# CANDataDiodeSchematic-STM32F0-Rev7.net
KiCad netlist of a schematic drawn in Altium Designer
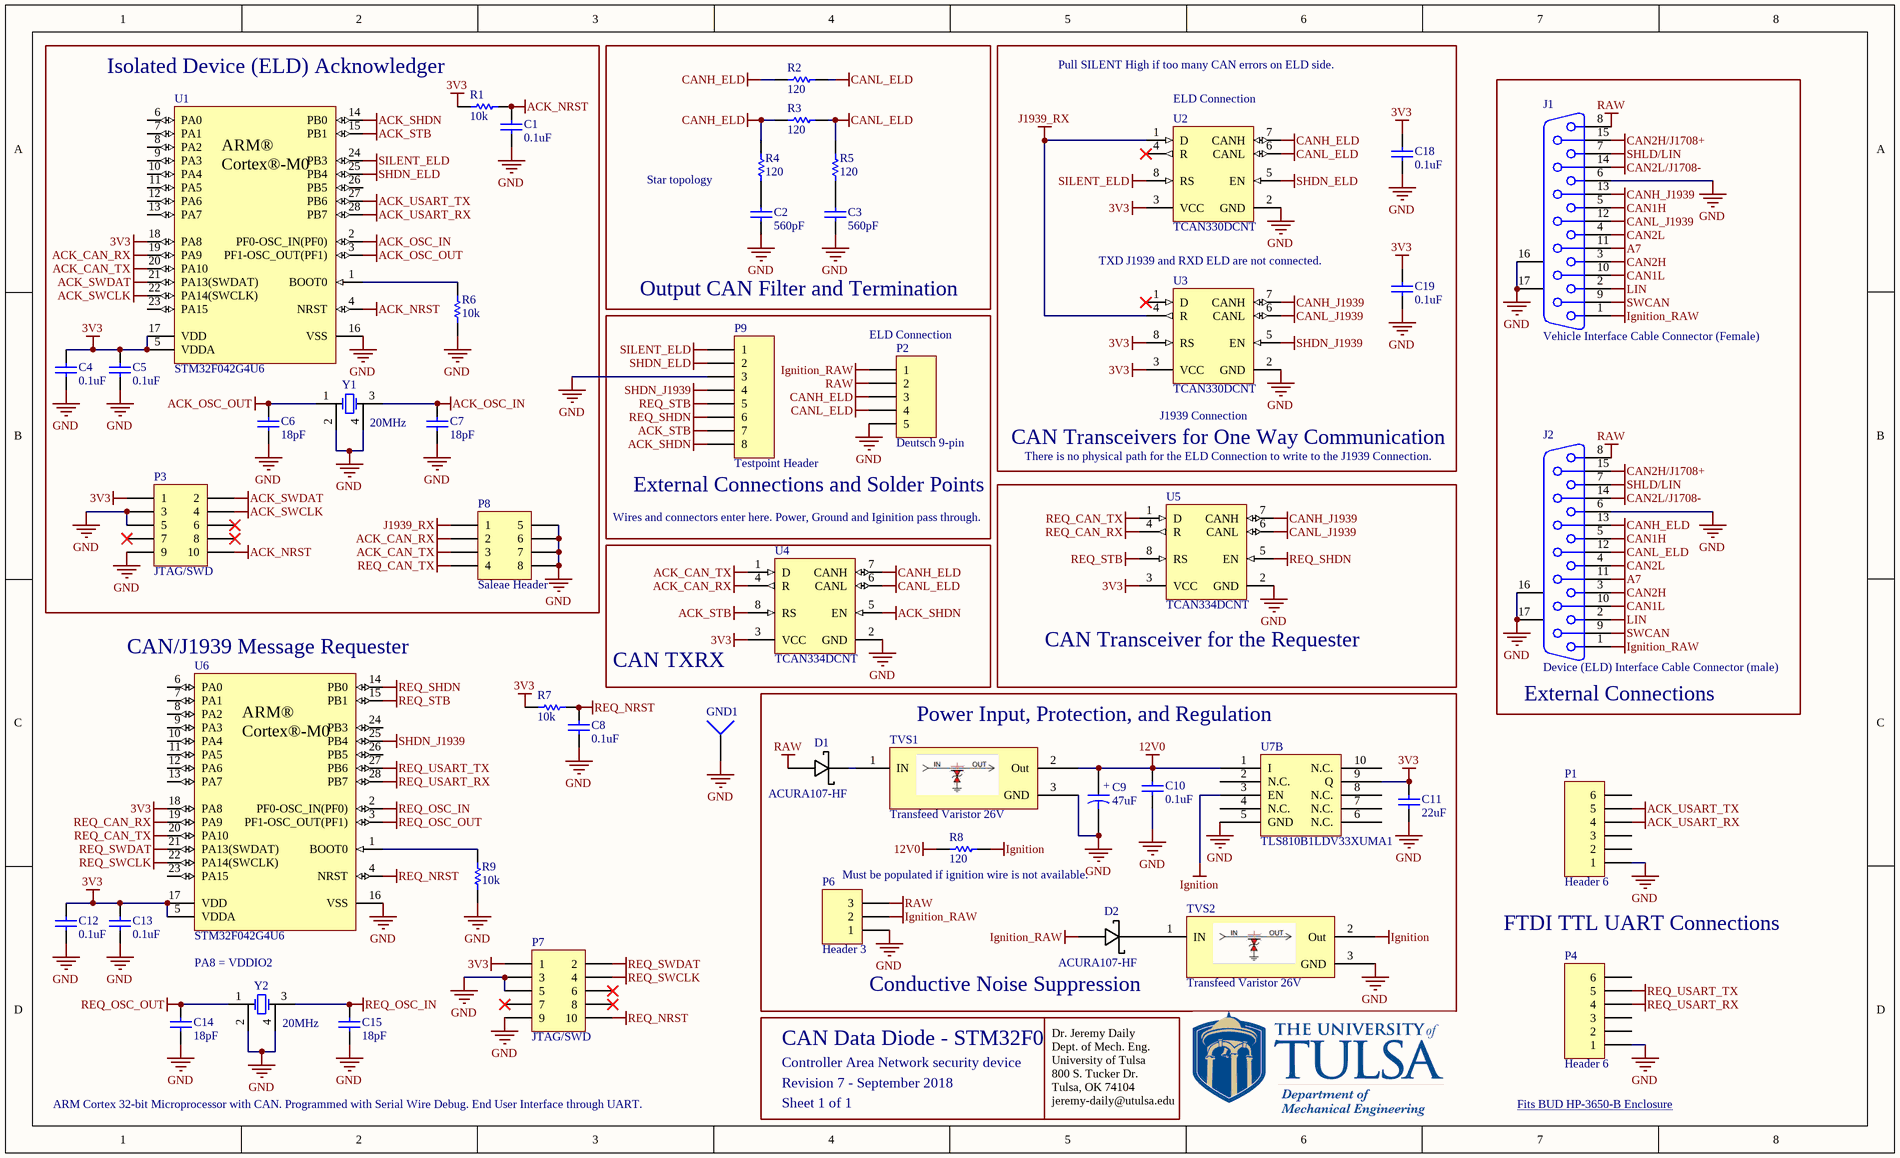
[diagram p0: CANDataDiodeSchematic-STM32F0-Rev7.SchDoc]

(export (version "E")
  (design (tool "Eeschema 10.0.6"))
  (components
    (comp (ref "C1")
      (value "0.1uF")
      (footprint "0402")
      (description "0.1µF ±10% 50V Ceramic Capacitor X7R 0402 (1005 Metric)")
      (fields
        (field (name "MANUFACTURER") "TDK Corporation")
        (field (name "PARTNUMBER") "CGA2B3X7R1H104K050BB")
      )
      (libsource (lib "SSS Integrated Library") (part "Cap"))
    )
    (comp (ref "C2")
      (value "560pF")
      (footprint "0402")
      (description "560pF ±5% 50V Ceramic Capacitor CH 0402 (1005 Metric)")
      (fields (field (name "MANUFACTURER") "Taiyo Yuden") (field (name "PARTNUMBER") "06031C561K4T2A"))
      (libsource (lib "SSS Integrated Library") (part "Cap"))
    )
    (comp (ref "C3")
      (value "560pF")
      (footprint "0402")
      (description "560pF ±5% 50V Ceramic Capacitor CH 0402 (1005 Metric)")
      (fields (field (name "MANUFACTURER") "Taiyo Yuden") (field (name "PARTNUMBER") "06031C561K4T2A"))
      (libsource (lib "SSS Integrated Library") (part "Cap"))
    )
    (comp (ref "C4")
      (value "0.1uF")
      (footprint "0402")
      (description "0.1µF ±10% 50V Ceramic Capacitor X7R 0402 (1005 Metric)")
      (fields
        (field (name "MANUFACTURER") "TDK Corporation")
        (field (name "PARTNUMBER") "CGA2B3X7R1H104K050BB")
      )
      (libsource (lib "SSS Integrated Library") (part "Cap"))
    )
    (comp (ref "C5")
      (value "0.1uF")
      (footprint "0402")
      (description "0.1µF ±10% 50V Ceramic Capacitor X7R 0402 (1005 Metric)")
      (fields
        (field (name "MANUFACTURER") "TDK Corporation")
        (field (name "PARTNUMBER") "CGA2B3X7R1H104K050BB")
      )
      (libsource (lib "SSS Integrated Library") (part "Cap"))
    )
    (comp (ref "C6")
      (value "18pF")
      (footprint "0402")
      (description "18pF ±5% 50V Ceramic Capacitor C0G, NP0 0402 (1005 Metric)")
      (fields
        (field (name "MANUFACTURER") "Murata Electronics North America")
        (field (name "PARTNUMBER") "GCM1555C1H180JA16D")
      )
      (libsource (lib "SSS Schematic Library") (part "Cap"))
    )
    (comp (ref "C7")
      (value "18pF")
      (footprint "0402")
      (description "18pF ±5% 50V Ceramic Capacitor C0G, NP0 0402 (1005 Metric)")
      (fields
        (field (name "MANUFACTURER") "Murata Electronics North America")
        (field (name "PARTNUMBER") "GCM1555C1H180JA16D")
      )
      (libsource (lib "SSS Schematic Library") (part "Cap"))
    )
    (comp (ref "C8")
      (value "0.1uF")
      (footprint "0402")
      (description "0.1µF ±10% 50V Ceramic Capacitor X7R 0402 (1005 Metric)")
      (fields
        (field (name "MANUFACTURER") "TDK Corporation")
        (field (name "PARTNUMBER") "CGA2B3X7R1H104K050BB")
      )
      (libsource (lib "SSS Integrated Library") (part "Cap"))
    )
    (comp (ref "C9")
      (value "47uF")
      (footprint "Elec. Cap - D")
      (description "47µF 35V Aluminum Capacitors Radial, Can - SMD 5000 Hrs @ 105°C")
      (fields
        (field (name "MANUFACTURER") "Panasonic Electronic Components")
        (field (name "PARTNUMBER") "EEE-HDV470XAP")
      )
      (libsource (lib "SSS Integrated Library") (part "Electrolytic Cap"))
    )
    (comp (ref "C10")
      (value "0.1uF")
      (footprint "0402")
      (description "0.1µF ±10% 50V Ceramic Capacitor X7R 0402 (1005 Metric)")
      (fields
        (field (name "MANUFACTURER") "TDK Corporation")
        (field (name "PARTNUMBER") "CGA2B3X7R1H104K050BB")
      )
      (libsource (lib "SSS Integrated Library") (part "Cap"))
    )
    (comp (ref "C11")
      (value "22uF")
      (footprint "1206")
      (description "22µF ±20% 4V Ceramic Capacitor X7R 1206 (3216 Metric)")
      (fields (field (name "MANUFACTURER") "Taiyo Yuden") (field (name "PARTNUMBER") "AMK316AB7226MLHT"))
      (libsource (lib "SSS Integrated Library") (part "Cap"))
    )
    (comp (ref "C12")
      (value "0.1uF")
      (footprint "0402")
      (description "0.1µF ±10% 50V Ceramic Capacitor X7R 0402 (1005 Metric)")
      (fields
        (field (name "MANUFACTURER") "TDK Corporation")
        (field (name "PARTNUMBER") "CGA2B3X7R1H104K050BB")
      )
      (libsource (lib "SSS Integrated Library") (part "Cap"))
    )
    (comp (ref "C13")
      (value "0.1uF")
      (footprint "0402")
      (description "0.1µF ±10% 50V Ceramic Capacitor X7R 0402 (1005 Metric)")
      (fields
        (field (name "MANUFACTURER") "TDK Corporation")
        (field (name "PARTNUMBER") "CGA2B3X7R1H104K050BB")
      )
      (libsource (lib "SSS Integrated Library") (part "Cap"))
    )
    (comp (ref "C14")
      (value "18pF")
      (footprint "0402")
      (description "18pF ±5% 50V Ceramic Capacitor C0G, NP0 0402 (1005 Metric)")
      (fields
        (field (name "MANUFACTURER") "Murata Electronics North America")
        (field (name "PARTNUMBER") "GCM1555C1H180JA16D")
      )
      (libsource (lib "SSS Schematic Library") (part "Cap"))
    )
    (comp (ref "C15")
      (value "18pF")
      (footprint "0402")
      (description "18pF ±5% 50V Ceramic Capacitor C0G, NP0 0402 (1005 Metric)")
      (fields
        (field (name "MANUFACTURER") "Murata Electronics North America")
        (field (name "PARTNUMBER") "GCM1555C1H180JA16D")
      )
      (libsource (lib "SSS Schematic Library") (part "Cap"))
    )
    (comp (ref "C18")
      (value "0.1uF")
      (footprint "0402")
      (description "0.1µF ±10% 50V Ceramic Capacitor X7R 0402 (1005 Metric)")
      (fields
        (field (name "MANUFACTURER") "TDK Corporation")
        (field (name "PARTNUMBER") "CGA2B3X7R1H104K050BB")
      )
      (libsource (lib "SSS Integrated Library") (part "Cap"))
    )
    (comp (ref "C19")
      (value "0.1uF")
      (footprint "0402")
      (description "0.1µF ±10% 50V Ceramic Capacitor X7R 0402 (1005 Metric)")
      (fields
        (field (name "MANUFACTURER") "TDK Corporation")
        (field (name "PARTNUMBER") "CGA2B3X7R1H104K050BB")
      )
      (libsource (lib "SSS Integrated Library") (part "Cap"))
    )
    (comp (ref "D1")
      (value "ACURA107-HF")
      (footprint "SMA with A and K")
      (description "Diode Schottky 1000V 1A Surface Mount DO-214AC (SMA)")
      (fields (field (name "MANUFACTURER") "Comchip Technology"))
      (libsource (lib "SSS Integrated Library") (part "Schottky Diode"))
    )
    (comp (ref "D2")
      (value "ACURA107-HF")
      (footprint "SMA with A and K")
      (description "Diode Schottky 1000V 1A Surface Mount DO-214AC (SMA)")
      (fields (field (name "MANUFACTURER") "Comchip Technology"))
      (libsource (lib "SSS Integrated Library") (part "Schottky Diode"))
    )
    (comp (ref "GND1")
      (value "Socket")
      (footprint "PIN1")
      (libsource (lib "Miscellaneous Connectors") (part "Socket"))
    )
    (comp (ref "J1")
      (value "Vehicle Interface Cable Connector (Female)")
      (footprint "DSUB1.385-2H15")
      (description "Receptacle Assembly, 15 Position, Right Angle")
      (fields (field (name "MANUFACTURER") "Amphenol FCI") (field (name "PARTNUMBER") "D15S33E4GV00LF"))
      (libsource (lib "Miscellaneous Connectors") (part "D Connector 15"))
    )
    (comp (ref "J2")
      (value "Device (ELD) Interface Cable Connector (male)")
      (footprint "DSUB1.385-2H15")
      (description "Receptacle Assembly, 15 Position, Right Angle")
      (fields (field (name "MANUFACTURER") "Amphenol FCI") (field (name "PARTNUMBER") "D15P33E4GV00LF"))
      (libsource (lib "Miscellaneous Connectors") (part "D Connector 15"))
    )
    (comp (ref "P1")
      (value "Header 6")
      (footprint "HDR1X6")
      (description "Header, 6-Pin")
      (fields
        (field (name "MANUFACTURER") "Sullins Connector Solutions")
        (field (name "PARTNUMBER") "PBC06SFAN")
      )
      (libsource (lib "Miscellaneous Connectors") (part "Header 6"))
    )
    (comp (ref "P2")
      (value "Deutsch 9-pin")
      (footprint "HDR1X5")
      (description "Pins A,B C, D oin the J1939 connector")
      (libsource (lib "Miscellaneous Connectors") (part "Header 5"))
    )
    (comp (ref "P3")
      (value "JTAG/SWD")
      (footprint "MHDR2X5")
      (description "Connector Header Through Hole 10 position 0.050\" (1.27mm)")
      (fields (field (name "MANUFACTURER") "CNC Tech") (field (name "PARTNUMBER") "1175-1627-ND"))
      (libsource (lib "Miscellaneous Connectors") (part "MHDR2X5"))
    )
    (comp (ref "P4")
      (value "Header 6")
      (footprint "HDR1X6")
      (description "Header, 6-Pin")
      (fields
        (field (name "MANUFACTURER") "Sullins Connector Solutions")
        (field (name "PARTNUMBER") "PBC06SFAN")
      )
      (libsource (lib "Miscellaneous Connectors") (part "Header 6"))
    )
    (comp (ref "P6")
      (value "Header 3")
      (footprint "HDR1X3")
      (description "Header, 3-Pin")
      (libsource (lib "Miscellaneous Connectors") (part "Header 3"))
    )
    (comp (ref "P7")
      (value "JTAG/SWD")
      (footprint "MHDR2X5")
      (description "Header, 5-Pin, Dual row")
      (fields (field (name "MANUFACTURER") "CNC Tech") (field (name "PARTNUMBER") "1175-1627-ND"))
      (libsource (lib "Miscellaneous Connectors") (part "MHDR2X5"))
    )
    (comp (ref "P8")
      (value "Saleae Header")
      (footprint "HDR2X4_CEN")
      (description "Header, 4-Pin, Dual row")
      (libsource (lib "Miscellaneous Connectors") (part "Header 4X2A"))
    )
    (comp (ref "P9")
      (value "Testpoint Header")
      (footprint "HDR1X8")
      (description "Header, 8-Pin")
      (libsource (lib "Miscellaneous Connectors") (part "Header 8"))
    )
    (comp (ref "R1")
      (value "10k")
      (footprint "0402")
      (fields (field (name "MANUFACTURER") "Susumu") (field (name "PARTNUMBER") "RG1005P-103-D-T10"))
      (libsource (lib "SSS Integrated Library") (part "Chip Resistor"))
    )
    (comp (ref "R2")
      (value "120")
      (footprint "0402")
      (description "120 Ohms ±1% 0.063W, 1/16W Chip Resistor 0402 (1005 Metric) Automotive AEC-Q200 Thick Film")
      (fields (field (name "MANUFACTURER") "Vishay Dale") (field (name "PARTNUMBER") "CRCW0402120RFKED"))
      (libsource (lib "SSS Integrated Library") (part "Chip Resistor"))
    )
    (comp (ref "R3")
      (value "120")
      (footprint "0402")
      (description "120 Ohms ±1% 0.063W, 1/16W Chip Resistor 0402 (1005 Metric) Automotive AEC-Q200 Thick Film")
      (fields (field (name "MANUFACTURER") "Vishay Dale") (field (name "PARTNUMBER") "CRCW0402120RFKED"))
      (libsource (lib "SSS Integrated Library") (part "Chip Resistor"))
    )
    (comp (ref "R4")
      (value "120")
      (footprint "0402")
      (description "120 Ohms ±1% 0.063W, 1/16W Chip Resistor 0402 (1005 Metric) Automotive AEC-Q200 Thick Film")
      (fields (field (name "MANUFACTURER") "Vishay Dale") (field (name "PARTNUMBER") "CRCW0402120RFKED"))
      (libsource (lib "SSS Integrated Library") (part "Chip Resistor"))
    )
    (comp (ref "R5")
      (value "120")
      (footprint "0402")
      (description "120 Ohms ±1% 0.063W, 1/16W Chip Resistor 0402 (1005 Metric) Automotive AEC-Q200 Thick Film")
      (fields (field (name "MANUFACTURER") "Vishay Dale") (field (name "PARTNUMBER") "CRCW0402120RFKED"))
      (libsource (lib "SSS Integrated Library") (part "Chip Resistor"))
    )
    (comp (ref "R6")
      (value "10k")
      (footprint "0402")
      (fields (field (name "MANUFACTURER") "Susumu") (field (name "PARTNUMBER") "RG1005P-103-D-T10"))
      (libsource (lib "SSS Integrated Library") (part "Chip Resistor"))
    )
    (comp (ref "R7")
      (value "10k")
      (footprint "0402")
      (fields (field (name "MANUFACTURER") "Susumu") (field (name "PARTNUMBER") "RG1005P-103-D-T10"))
      (libsource (lib "SSS Integrated Library") (part "Chip Resistor"))
    )
    (comp (ref "R8")
      (value "120")
      (footprint "0402")
      (description "120 Ohms ±1% 0.063W, 1/16W Chip Resistor 0402 (1005 Metric) Automotive AEC-Q200 Thick Film")
      (fields (field (name "MANUFACTURER") "Vishay Dale") (field (name "PARTNUMBER") "CRCW0402120RFKED"))
      (libsource (lib "SSS Integrated Library") (part "Chip Resistor"))
    )
    (comp (ref "R9")
      (value "10k")
      (footprint "0402")
      (fields (field (name "MANUFACTURER") "Susumu") (field (name "PARTNUMBER") "RG1005P-103-D-T10"))
      (libsource (lib "SSS Integrated Library") (part "Chip Resistor"))
    )
    (comp (ref "TVS1")
      (value "Transfeed Varistor 26V")
      (footprint "Transfeed")
      (description "34.5V 80A Varistor 1 Circuit Surface Mount 0805 (2012 Metric)")
      (fields (field (name "MANUFACTURER") "AVX") (field (name "PARTNUMBER") "V2AF126C600Y2EDP"))
      (libsource (lib "TU Custom Parts Schematics") (part "Transfeed"))
    )
    (comp (ref "TVS2")
      (value "Transfeed Varistor 26V")
      (footprint "Transfeed")
      (description "34.5V 80A Varistor 1 Circuit Surface Mount 0805 (2012 Metric)")
      (fields (field (name "MANUFACTURER") "AVX") (field (name "PARTNUMBER") "V2AF126C600Y2EDP"))
      (libsource (lib "TU Custom Parts Schematics") (part "Transfeed"))
    )
    (comp (ref "U1")
      (value "STM32F042G4U6")
      (footprint "STM-UFQFPN28_V")
      (description "ARM® Cortex®-M0 STM32F0 Microcontroller IC 32-Bit 48MHz 16KB (16K x 8) FLASH 28-UFQFPN (4x4)")
      (fields (field (name "MANUFACTURER") "STMicroelectronics"))
      (libsource (lib "STMicroelectronics STM32 F0") (part "STM32F050G4U6"))
    )
    (comp (ref "U2")
      (value "TCAN330DCNT")
      (footprint "SOT65P280X145-8N")
      (description "IC TXRX CAN 3.3V SOT23-8")
      (fields (field (name "MANUFACTURER") "Texas Instruments"))
      (libsource (lib "Texas Instruments Interface CAN") (part "SN65HVD234DR"))
    )
    (comp (ref "U3")
      (value "TCAN330DCNT")
      (footprint "SOT65P280X145-8N")
      (description "IC TXRX CAN 3.3V SOT23-8")
      (fields (field (name "MANUFACTURER") "Texas Instruments"))
      (libsource (lib "Texas Instruments Interface CAN") (part "SN65HVD234DR"))
    )
    (comp (ref "U4")
      (value "TCAN334DCNT")
      (footprint "SOT65P280X145-8N")
      (description "IC TXRX CAN 3.3V SOT23-8")
      (fields (field (name "MANUFACTURER") "Texas Instruments"))
      (libsource (lib "Texas Instruments Interface CAN") (part "SN65HVD234DR"))
    )
    (comp (ref "U5")
      (value "TCAN334DCNT")
      (footprint "SOT65P280X145-8N")
      (description "IC TXRX CAN 3.3V SOT23-8")
      (fields (field (name "MANUFACTURER") "Texas Instruments"))
      (libsource (lib "Texas Instruments Interface CAN") (part "SN65HVD234DR"))
    )
    (comp (ref "U6")
      (value "STM32F042G4U6")
      (footprint "STM-UFQFPN28_V")
      (description "ARM® Cortex®-M0 STM32F0 Microcontroller IC 32-Bit 48MHz 16KB (16K x 8) FLASH 28-UFQFPN (4x4)")
      (fields (field (name "MANUFACTURER") "STMicroelectronics"))
      (libsource (lib "STMicroelectronics STM32 F0") (part "STM32F050G4U6"))
    )
    (comp (ref "U7")
      (value "TLS810B1LDV33XUMA1")
      (footprint "SON50P330X110_HS-11N")
      (description "Linear Voltage Regulator IC  1 Output  100mA PG-TSON-10")
      (fields (field (name "MANUFACTURER") "Infineon Technologies"))
      (libsource (lib "CANDataDiode Schematic Library") (part "TLS810B1"))
    )
    (comp (ref "Y1")
      (value "20MHz")
      (footprint "XTAL 4 pad")
      (description "20MHz ±30ppm Crystal 18pF 60 Ohms 4-SMD, No Lead")
      (fields (field (name "MANUFACTURER") "ECS Inc.") (field (name "PARTNUMBER") "ECS-200-18-33Q-DS"))
      (libsource (lib "TU Custom Parts Schematics") (part "Crystal with Ground"))
    )
    (comp (ref "Y2")
      (value "20MHz")
      (footprint "XTAL 4 pad")
      (description "20MHz ±30ppm Crystal 18pF 60 Ohms 4-SMD, No Lead")
      (fields (field (name "MANUFACTURER") "ECS Inc.") (field (name "PARTNUMBER") "ECS-200-18-33Q-DS"))
      (libsource (lib "TU Custom Parts Schematics") (part "Crystal with Ground"))
    )
  )
  (nets
    (net (code "1") (name "3V3") (class "Default")
      (node (ref "C11") (pin "2") (pinfunction "2_2") (pintype "passive"))
      (node (ref "C12") (pin "2") (pinfunction "2_2") (pintype "passive"))
      (node (ref "C13") (pin "2") (pinfunction "2_2") (pintype "passive"))
      (node (ref "C18") (pin "2") (pinfunction "2_2") (pintype "passive"))
      (node (ref "C19") (pin "2") (pinfunction "2_2") (pintype "passive"))
      (node (ref "C4") (pin "2") (pinfunction "2_2") (pintype "passive"))
      (node (ref "C5") (pin "2") (pinfunction "2_2") (pintype "passive"))
      (node (ref "P3") (pin "1") (pinfunction "1_1") (pintype "passive"))
      (node (ref "P7") (pin "1") (pinfunction "1_1") (pintype "passive"))
      (node (ref "R1") (pin "2") (pinfunction "2_2") (pintype "passive"))
      (node (ref "R7") (pin "2") (pinfunction "2_2") (pintype "passive"))
      (node (ref "U1") (pin "17") (pinfunction "VDD_17") (pintype "power_in"))
      (node (ref "U1") (pin "18") (pinfunction "PA8_18") (pintype "bidirectional"))
      (node (ref "U1") (pin "5") (pinfunction "VDDA_5") (pintype "power_in"))
      (node (ref "U2") (pin "3") (pinfunction "VCC_3") (pintype "power_in"))
      (node (ref "U3") (pin "3") (pinfunction "VCC_3") (pintype "power_in"))
      (node (ref "U3") (pin "8") (pinfunction "RS_8") (pintype "input"))
      (node (ref "U4") (pin "3") (pinfunction "VCC_3") (pintype "power_in"))
      (node (ref "U5") (pin "3") (pinfunction "VCC_3") (pintype "power_in"))
      (node (ref "U6") (pin "17") (pinfunction "VDD_17") (pintype "power_in"))
      (node (ref "U6") (pin "18") (pinfunction "PA8_18") (pintype "bidirectional"))
      (node (ref "U6") (pin "5") (pinfunction "VDDA_5") (pintype "power_in"))
      (node (ref "U7") (pin "9") (pinfunction "Q_9") (pintype "passive"))
    )
    (net (code "2") (name "12V0") (class "Default")
      (node (ref "C10") (pin "2") (pinfunction "2_2") (pintype "passive"))
      (node (ref "C9") (pin "1") (pinfunction "1_1") (pintype "passive"))
      (node (ref "R8") (pin "1") (pinfunction "1_1") (pintype "passive"))
      (node (ref "TVS1") (pin "2") (pinfunction "Out_2") (pintype "passive"))
      (node (ref "U7") (pin "1") (pinfunction "I_1") (pintype "passive"))
    )
    (net (code "3") (name "A7") (class "Default")
      (node (ref "J1") (pin "11") (pinfunction "11_11") (pintype "passive"))
      (node (ref "J2") (pin "11") (pinfunction "11_11") (pintype "passive"))
    )
    (net (code "4") (name "ACK_CAN_RX") (class "Default")
      (node (ref "P8") (pin "2") (pinfunction "2_2") (pintype "passive"))
      (node (ref "U1") (pin "19") (pinfunction "PA9_19") (pintype "bidirectional"))
      (node (ref "U4") (pin "4") (pinfunction "R_4") (pintype "output"))
    )
    (net (code "5") (name "ACK_CAN_TX") (class "Default")
      (node (ref "P8") (pin "3") (pinfunction "3_3") (pintype "passive"))
      (node (ref "U1") (pin "20") (pinfunction "PA10_20") (pintype "bidirectional"))
      (node (ref "U4") (pin "1") (pinfunction "D_1") (pintype "input"))
    )
    (net (code "6") (name "ACK_NRST") (class "Default")
      (node (ref "C1") (pin "2") (pinfunction "2_2") (pintype "passive"))
      (node (ref "P3") (pin "10") (pinfunction "10_10") (pintype "passive"))
      (node (ref "R1") (pin "1") (pinfunction "1_1") (pintype "passive"))
      (node (ref "U1") (pin "4") (pinfunction "NRST_4") (pintype "bidirectional"))
    )
    (net (code "7") (name "ACK_OSC_IN") (class "Default")
      (node (ref "C7") (pin "1") (pinfunction "1_1") (pintype "passive"))
      (node (ref "U1") (pin "2") (pinfunction "PF0-OSC_IN(PF0)_2") (pintype "bidirectional"))
      (node (ref "Y1") (pin "3") (pinfunction "OSC2_3") (pintype "passive"))
    )
    (net (code "8") (name "ACK_OSC_OUT") (class "Default")
      (node (ref "C6") (pin "2") (pinfunction "2_2") (pintype "passive"))
      (node (ref "U1") (pin "3") (pinfunction "PF1-OSC_OUT(PF1)_3") (pintype "bidirectional"))
      (node (ref "Y1") (pin "1") (pinfunction "OSC1_1") (pintype "passive"))
    )
    (net (code "9") (name "ACK_SHDN") (class "Default")
      (node (ref "P9") (pin "8") (pinfunction "8_8") (pintype "passive"))
      (node (ref "U1") (pin "14") (pinfunction "PB0_14") (pintype "bidirectional"))
      (node (ref "U4") (pin "5") (pinfunction "EN_5") (pintype "input"))
    )
    (net (code "10") (name "ACK_STB") (class "Default")
      (node (ref "P9") (pin "7") (pinfunction "7_7") (pintype "passive"))
      (node (ref "U1") (pin "15") (pinfunction "PB1_15") (pintype "bidirectional"))
      (node (ref "U4") (pin "8") (pinfunction "RS_8") (pintype "input"))
    )
    (net (code "11") (name "ACK_SWCLK") (class "Default")
      (node (ref "P3") (pin "4") (pinfunction "4_4") (pintype "passive"))
      (node (ref "U1") (pin "22") (pinfunction "PA14(SWCLK)_22") (pintype "bidirectional"))
    )
    (net (code "12") (name "ACK_SWDAT") (class "Default")
      (node (ref "P3") (pin "2") (pinfunction "2_2") (pintype "passive"))
      (node (ref "U1") (pin "21") (pinfunction "PA13(SWDAT)_21") (pintype "bidirectional"))
    )
    (net (code "13") (name "ACK_USART_RX") (class "Default")
      (node (ref "P1") (pin "4") (pinfunction "4_4") (pintype "passive"))
      (node (ref "U1") (pin "28") (pinfunction "PB7_28") (pintype "bidirectional"))
    )
    (net (code "14") (name "ACK_USART_TX") (class "Default")
      (node (ref "P1") (pin "5") (pinfunction "5_5") (pintype "passive"))
      (node (ref "U1") (pin "27") (pinfunction "PB6_27") (pintype "bidirectional"))
    )
    (net (code "15") (name "CAN1H") (class "Default")
      (node (ref "J1") (pin "5") (pinfunction "5_5") (pintype "passive"))
      (node (ref "J2") (pin "5") (pinfunction "5_5") (pintype "passive"))
    )
    (net (code "16") (name "CAN1L") (class "Default")
      (node (ref "J1") (pin "10") (pinfunction "10_10") (pintype "passive"))
      (node (ref "J2") (pin "10") (pinfunction "10_10") (pintype "passive"))
    )
    (net (code "17") (name "CAN2H") (class "Default")
      (node (ref "J1") (pin "3") (pinfunction "3_3") (pintype "passive"))
      (node (ref "J2") (pin "3") (pinfunction "3_3") (pintype "passive"))
    )
    (net (code "18") (name "CAN2H{slash}J1708+") (class "Default")
      (node (ref "J1") (pin "15") (pinfunction "15_15") (pintype "passive"))
      (node (ref "J2") (pin "15") (pinfunction "15_15") (pintype "passive"))
    )
    (net (code "19") (name "CAN2L") (class "Default")
      (node (ref "J1") (pin "4") (pinfunction "4_4") (pintype "passive"))
      (node (ref "J2") (pin "4") (pinfunction "4_4") (pintype "passive"))
    )
    (net (code "20") (name "CAN2L{slash}J1708-") (class "Default")
      (node (ref "J1") (pin "14") (pinfunction "14_14") (pintype "passive"))
      (node (ref "J2") (pin "14") (pinfunction "14_14") (pintype "passive"))
    )
    (net (code "21") (name "CANH_ELD") (class "Default")
      (node (ref "J2") (pin "13") (pinfunction "13_13") (pintype "passive"))
      (node (ref "P2") (pin "3") (pinfunction "3_3") (pintype "passive"))
      (node (ref "R2") (pin "2") (pinfunction "2_2") (pintype "passive"))
      (node (ref "R3") (pin "2") (pinfunction "2_2") (pintype "passive"))
      (node (ref "R4") (pin "1") (pinfunction "1_1") (pintype "passive"))
      (node (ref "U2") (pin "7") (pinfunction "CANH_7") (pintype "bidirectional"))
      (node (ref "U4") (pin "7") (pinfunction "CANH_7") (pintype "bidirectional"))
    )
    (net (code "22") (name "CANH_J1939") (class "Default")
      (node (ref "J1") (pin "13") (pinfunction "13_13") (pintype "passive"))
      (node (ref "U3") (pin "7") (pinfunction "CANH_7") (pintype "bidirectional"))
      (node (ref "U5") (pin "7") (pinfunction "CANH_7") (pintype "bidirectional"))
    )
    (net (code "23") (name "CANL_ELD") (class "Default")
      (node (ref "J2") (pin "12") (pinfunction "12_12") (pintype "passive"))
      (node (ref "P2") (pin "4") (pinfunction "4_4") (pintype "passive"))
      (node (ref "R2") (pin "1") (pinfunction "1_1") (pintype "passive"))
      (node (ref "R3") (pin "1") (pinfunction "1_1") (pintype "passive"))
      (node (ref "R5") (pin "1") (pinfunction "1_1") (pintype "passive"))
      (node (ref "U2") (pin "6") (pinfunction "CANL_6") (pintype "bidirectional"))
      (node (ref "U4") (pin "6") (pinfunction "CANL_6") (pintype "bidirectional"))
    )
    (net (code "24") (name "CANL_J1939") (class "Default")
      (node (ref "J1") (pin "12") (pinfunction "12_12") (pintype "passive"))
      (node (ref "U3") (pin "6") (pinfunction "CANL_6") (pintype "bidirectional"))
      (node (ref "U5") (pin "6") (pinfunction "CANL_6") (pintype "bidirectional"))
    )
    (net (code "25") (name "GND") (class "Default")
      (node (ref "C1") (pin "1") (pinfunction "1_1") (pintype "passive"))
      (node (ref "C10") (pin "1") (pinfunction "1_1") (pintype "passive"))
      (node (ref "C11") (pin "1") (pinfunction "1_1") (pintype "passive"))
      (node (ref "C12") (pin "1") (pinfunction "1_1") (pintype "passive"))
      (node (ref "C13") (pin "1") (pinfunction "1_1") (pintype "passive"))
      (node (ref "C14") (pin "1") (pinfunction "1_1") (pintype "passive"))
      (node (ref "C15") (pin "2") (pinfunction "2_2") (pintype "passive"))
      (node (ref "C18") (pin "1") (pinfunction "1_1") (pintype "passive"))
      (node (ref "C19") (pin "1") (pinfunction "1_1") (pintype "passive"))
      (node (ref "C2") (pin "1") (pinfunction "1_1") (pintype "passive"))
      (node (ref "C3") (pin "1") (pinfunction "1_1") (pintype "passive"))
      (node (ref "C4") (pin "1") (pinfunction "1_1") (pintype "passive"))
      (node (ref "C5") (pin "1") (pinfunction "1_1") (pintype "passive"))
      (node (ref "C6") (pin "1") (pinfunction "1_1") (pintype "passive"))
      (node (ref "C7") (pin "2") (pinfunction "2_2") (pintype "passive"))
      (node (ref "C8") (pin "1") (pinfunction "1_1") (pintype "passive"))
      (node (ref "C9") (pin "2") (pinfunction "-_2") (pintype "passive"))
      (node (ref "GND1") (pin "1") (pinfunction "1_1") (pintype "passive"))
      (node (ref "J1") (pin "16") (pinfunction "MH1_16") (pintype "passive"))
      (node (ref "J1") (pin "17") (pinfunction "MH2_17") (pintype "passive"))
      (node (ref "J1") (pin "6") (pinfunction "6_6") (pintype "passive"))
      (node (ref "J2") (pin "16") (pinfunction "MH1_16") (pintype "passive"))
      (node (ref "J2") (pin "17") (pinfunction "MH2_17") (pintype "passive"))
      (node (ref "J2") (pin "6") (pinfunction "6_6") (pintype "passive"))
      (node (ref "P1") (pin "1") (pinfunction "1_1") (pintype "passive"))
      (node (ref "P2") (pin "5") (pinfunction "5_5") (pintype "passive"))
      (node (ref "P3") (pin "3") (pinfunction "3_3") (pintype "passive"))
      (node (ref "P3") (pin "5") (pinfunction "5_5") (pintype "passive"))
      (node (ref "P3") (pin "9") (pinfunction "9_9") (pintype "passive"))
      (node (ref "P4") (pin "1") (pinfunction "1_1") (pintype "passive"))
      (node (ref "P6") (pin "1") (pinfunction "1_1") (pintype "passive"))
      (node (ref "P7") (pin "3") (pinfunction "3_3") (pintype "passive"))
      (node (ref "P7") (pin "5") (pinfunction "5_5") (pintype "passive"))
      (node (ref "P7") (pin "9") (pinfunction "9_9") (pintype "passive"))
      (node (ref "P8") (pin "5") (pinfunction "5_5") (pintype "passive"))
      (node (ref "P8") (pin "6") (pinfunction "6_6") (pintype "passive"))
      (node (ref "P8") (pin "7") (pinfunction "7_7") (pintype "passive"))
      (node (ref "P8") (pin "8") (pinfunction "8_8") (pintype "passive"))
      (node (ref "P9") (pin "3") (pinfunction "3_3") (pintype "passive"))
      (node (ref "R6") (pin "1") (pinfunction "1_1") (pintype "passive"))
      (node (ref "R9") (pin "1") (pinfunction "1_1") (pintype "passive"))
      (node (ref "TVS1") (pin "3") (pinfunction "GND_3") (pintype "passive"))
      (node (ref "TVS2") (pin "3") (pinfunction "GND_3") (pintype "passive"))
      (node (ref "U1") (pin "16") (pinfunction "VSS_16") (pintype "power_in"))
      (node (ref "U2") (pin "2") (pinfunction "GND_2") (pintype "power_in"))
      (node (ref "U3") (pin "2") (pinfunction "GND_2") (pintype "power_in"))
      (node (ref "U4") (pin "2") (pinfunction "GND_2") (pintype "power_in"))
      (node (ref "U5") (pin "2") (pinfunction "GND_2") (pintype "power_in"))
      (node (ref "U6") (pin "16") (pinfunction "VSS_16") (pintype "power_in"))
      (node (ref "U7") (pin "5") (pinfunction "GND_5") (pintype "passive"))
      (node (ref "Y1") (pin "2") (pinfunction "OSC2_2") (pintype "passive"))
      (node (ref "Y1") (pin "4") (pinfunction "GND_4") (pintype "passive"))
      (node (ref "Y2") (pin "2") (pinfunction "OSC2_2") (pintype "passive"))
      (node (ref "Y2") (pin "4") (pinfunction "GND_4") (pintype "passive"))
    )
    (net (code "26") (name "Ignition") (class "Default")
      (node (ref "R8") (pin "2") (pinfunction "2_2") (pintype "passive"))
      (node (ref "TVS2") (pin "2") (pinfunction "Out_2") (pintype "passive"))
      (node (ref "U7") (pin "3") (pinfunction "EN_3") (pintype "passive"))
    )
    (net (code "27") (name "Ignition_RAW") (class "Default")
      (node (ref "D2") (pin "1") (pinfunction "A_1") (pintype "passive"))
      (node (ref "J1") (pin "1") (pinfunction "1_1") (pintype "passive"))
      (node (ref "J2") (pin "1") (pinfunction "1_1") (pintype "passive"))
      (node (ref "P2") (pin "1") (pinfunction "1_1") (pintype "passive"))
      (node (ref "P6") (pin "2") (pinfunction "2_2") (pintype "passive"))
    )
    (net (code "28") (name "J1939_RX") (class "Default")
      (node (ref "P8") (pin "1") (pinfunction "1_1") (pintype "passive"))
      (node (ref "U2") (pin "1") (pinfunction "D_1") (pintype "input"))
      (node (ref "U3") (pin "4") (pinfunction "R_4") (pintype "output"))
    )
    (net (code "29") (name "LIN") (class "Default")
      (node (ref "J1") (pin "2") (pinfunction "2_2") (pintype "passive"))
      (node (ref "J2") (pin "2") (pinfunction "2_2") (pintype "passive"))
    )
    (net (code "30") (name "Net-(C2-Pad2)") (class "Default")
      (node (ref "C2") (pin "2") (pinfunction "2_2") (pintype "passive"))
      (node (ref "R4") (pin "2") (pinfunction "2_2") (pintype "passive"))
    )
    (net (code "31") (name "Net-(C3-Pad2)") (class "Default")
      (node (ref "C3") (pin "2") (pinfunction "2_2") (pintype "passive"))
      (node (ref "R5") (pin "2") (pinfunction "2_2") (pintype "passive"))
    )
    (net (code "32") (name "Net-(D1-K)") (class "Default")
      (node (ref "D1") (pin "2") (pinfunction "K_2") (pintype "passive"))
      (node (ref "TVS1") (pin "1") (pinfunction "IN_1") (pintype "passive"))
    )
    (net (code "33") (name "Net-(D2-K)") (class "Default")
      (node (ref "D2") (pin "2") (pinfunction "K_2") (pintype "passive"))
      (node (ref "TVS2") (pin "1") (pinfunction "IN_1") (pintype "passive"))
    )
    (net (code "34") (name "Net-(U1-BOOT0)") (class "Default")
      (node (ref "R6") (pin "2") (pinfunction "2_2") (pintype "passive"))
      (node (ref "U1") (pin "1") (pinfunction "BOOT0_1") (pintype "input"))
    )
    (net (code "35") (name "Net-(U6-BOOT0)") (class "Default")
      (node (ref "R9") (pin "2") (pinfunction "2_2") (pintype "passive"))
      (node (ref "U6") (pin "1") (pinfunction "BOOT0_1") (pintype "input"))
    )
    (net (code "36") (name "RAW") (class "Default")
      (node (ref "D1") (pin "1") (pinfunction "A_1") (pintype "passive"))
      (node (ref "J1") (pin "8") (pinfunction "8_8") (pintype "passive"))
      (node (ref "J2") (pin "8") (pinfunction "8_8") (pintype "passive"))
      (node (ref "P2") (pin "2") (pinfunction "2_2") (pintype "passive"))
      (node (ref "P6") (pin "3") (pinfunction "3_3") (pintype "passive"))
    )
    (net (code "37") (name "REQ_CAN_RX") (class "Default")
      (node (ref "U5") (pin "4") (pinfunction "R_4") (pintype "output"))
      (node (ref "U6") (pin "19") (pinfunction "PA9_19") (pintype "bidirectional"))
    )
    (net (code "38") (name "REQ_CAN_TX") (class "Default")
      (node (ref "P8") (pin "4") (pinfunction "4_4") (pintype "passive"))
      (node (ref "U5") (pin "1") (pinfunction "D_1") (pintype "input"))
      (node (ref "U6") (pin "20") (pinfunction "PA10_20") (pintype "bidirectional"))
    )
    (net (code "39") (name "REQ_NRST") (class "Default")
      (node (ref "C8") (pin "2") (pinfunction "2_2") (pintype "passive"))
      (node (ref "P7") (pin "10") (pinfunction "10_10") (pintype "passive"))
      (node (ref "R7") (pin "1") (pinfunction "1_1") (pintype "passive"))
      (node (ref "U6") (pin "4") (pinfunction "NRST_4") (pintype "bidirectional"))
    )
    (net (code "40") (name "REQ_OSC_IN") (class "Default")
      (node (ref "C15") (pin "1") (pinfunction "1_1") (pintype "passive"))
      (node (ref "U6") (pin "2") (pinfunction "PF0-OSC_IN(PF0)_2") (pintype "bidirectional"))
      (node (ref "Y2") (pin "3") (pinfunction "OSC2_3") (pintype "passive"))
    )
    (net (code "41") (name "REQ_OSC_OUT") (class "Default")
      (node (ref "C14") (pin "2") (pinfunction "2_2") (pintype "passive"))
      (node (ref "U6") (pin "3") (pinfunction "PF1-OSC_OUT(PF1)_3") (pintype "bidirectional"))
      (node (ref "Y2") (pin "1") (pinfunction "OSC1_1") (pintype "passive"))
    )
    (net (code "42") (name "REQ_SHDN") (class "Default")
      (node (ref "P9") (pin "6") (pinfunction "6_6") (pintype "passive"))
      (node (ref "U5") (pin "5") (pinfunction "EN_5") (pintype "input"))
      (node (ref "U6") (pin "14") (pinfunction "PB0_14") (pintype "bidirectional"))
    )
    (net (code "43") (name "REQ_STB") (class "Default")
      (node (ref "P9") (pin "5") (pinfunction "5_5") (pintype "passive"))
      (node (ref "U5") (pin "8") (pinfunction "RS_8") (pintype "input"))
      (node (ref "U6") (pin "15") (pinfunction "PB1_15") (pintype "bidirectional"))
    )
    (net (code "44") (name "REQ_SWCLK") (class "Default")
      (node (ref "P7") (pin "4") (pinfunction "4_4") (pintype "passive"))
      (node (ref "U6") (pin "22") (pinfunction "PA14(SWCLK)_22") (pintype "bidirectional"))
    )
    (net (code "45") (name "REQ_SWDAT") (class "Default")
      (node (ref "P7") (pin "2") (pinfunction "2_2") (pintype "passive"))
      (node (ref "U6") (pin "21") (pinfunction "PA13(SWDAT)_21") (pintype "bidirectional"))
    )
    (net (code "46") (name "REQ_USART_RX") (class "Default")
      (node (ref "P4") (pin "4") (pinfunction "4_4") (pintype "passive"))
      (node (ref "U6") (pin "28") (pinfunction "PB7_28") (pintype "bidirectional"))
    )
    (net (code "47") (name "REQ_USART_TX") (class "Default")
      (node (ref "P4") (pin "5") (pinfunction "5_5") (pintype "passive"))
      (node (ref "U6") (pin "27") (pinfunction "PB6_27") (pintype "bidirectional"))
    )
    (net (code "48") (name "SHDN_ELD") (class "Default")
      (node (ref "P9") (pin "2") (pinfunction "2_2") (pintype "passive"))
      (node (ref "U1") (pin "25") (pinfunction "PB4_25") (pintype "bidirectional"))
      (node (ref "U2") (pin "5") (pinfunction "EN_5") (pintype "input"))
    )
    (net (code "49") (name "SHDN_J1939") (class "Default")
      (node (ref "P9") (pin "4") (pinfunction "4_4") (pintype "passive"))
      (node (ref "U3") (pin "5") (pinfunction "EN_5") (pintype "input"))
      (node (ref "U6") (pin "25") (pinfunction "PB4_25") (pintype "bidirectional"))
    )
    (net (code "50") (name "SHLD{slash}LIN") (class "Default")
      (node (ref "J1") (pin "7") (pinfunction "7_7") (pintype "passive"))
      (node (ref "J2") (pin "7") (pinfunction "7_7") (pintype "passive"))
    )
    (net (code "51") (name "SILENT_ELD") (class "Default")
      (node (ref "P9") (pin "1") (pinfunction "1_1") (pintype "passive"))
      (node (ref "U1") (pin "24") (pinfunction "PB3_24") (pintype "bidirectional"))
      (node (ref "U2") (pin "8") (pinfunction "RS_8") (pintype "input"))
    )
    (net (code "52") (name "SWCAN") (class "Default")
      (node (ref "J1") (pin "9") (pinfunction "9_9") (pintype "passive"))
      (node (ref "J2") (pin "9") (pinfunction "9_9") (pintype "passive"))
    )
    (net (code "53") (name "unconnected-(P1-Pad2)") (class "Default")
      (node (ref "P1") (pin "2") (pinfunction "2_2") (pintype "passive"))
    )
    (net (code "54") (name "unconnected-(P1-Pad3)") (class "Default")
      (node (ref "P1") (pin "3") (pinfunction "3_3") (pintype "passive"))
    )
    (net (code "55") (name "unconnected-(P1-Pad6)") (class "Default")
      (node (ref "P1") (pin "6") (pinfunction "6_6") (pintype "passive"))
    )
    (net (code "56") (name "unconnected-(P3-Pad6)") (class "Default")
      (node (ref "P3") (pin "6") (pinfunction "6_6") (pintype "passive+no_connect"))
    )
    (net (code "57") (name "unconnected-(P3-Pad7)") (class "Default")
      (node (ref "P3") (pin "7") (pinfunction "7_7") (pintype "passive+no_connect"))
    )
    (net (code "58") (name "unconnected-(P3-Pad8)") (class "Default")
      (node (ref "P3") (pin "8") (pinfunction "8_8") (pintype "passive+no_connect"))
    )
    (net (code "59") (name "unconnected-(P4-Pad2)") (class "Default")
      (node (ref "P4") (pin "2") (pinfunction "2_2") (pintype "passive"))
    )
    (net (code "60") (name "unconnected-(P4-Pad3)") (class "Default")
      (node (ref "P4") (pin "3") (pinfunction "3_3") (pintype "passive"))
    )
    (net (code "61") (name "unconnected-(P4-Pad6)") (class "Default")
      (node (ref "P4") (pin "6") (pinfunction "6_6") (pintype "passive"))
    )
    (net (code "62") (name "unconnected-(P7-Pad6)") (class "Default")
      (node (ref "P7") (pin "6") (pinfunction "6_6") (pintype "passive+no_connect"))
    )
    (net (code "63") (name "unconnected-(P7-Pad7)") (class "Default")
      (node (ref "P7") (pin "7") (pinfunction "7_7") (pintype "passive+no_connect"))
    )
    (net (code "64") (name "unconnected-(P7-Pad8)") (class "Default")
      (node (ref "P7") (pin "8") (pinfunction "8_8") (pintype "passive+no_connect"))
    )
    (net (code "65") (name "unconnected-(U1-PA0-Pad6)") (class "Default")
      (node (ref "U1") (pin "6") (pinfunction "PA0_6") (pintype "bidirectional"))
    )
    (net (code "66") (name "unconnected-(U1-PA1-Pad7)") (class "Default")
      (node (ref "U1") (pin "7") (pinfunction "PA1_7") (pintype "bidirectional"))
    )
    (net (code "67") (name "unconnected-(U1-PA2-Pad8)") (class "Default")
      (node (ref "U1") (pin "8") (pinfunction "PA2_8") (pintype "bidirectional"))
    )
    (net (code "68") (name "unconnected-(U1-PA3-Pad9)") (class "Default")
      (node (ref "U1") (pin "9") (pinfunction "PA3_9") (pintype "bidirectional"))
    )
    (net (code "69") (name "unconnected-(U1-PA4-Pad10)") (class "Default")
      (node (ref "U1") (pin "10") (pinfunction "PA4_10") (pintype "bidirectional"))
    )
    (net (code "70") (name "unconnected-(U1-PA5-Pad11)") (class "Default")
      (node (ref "U1") (pin "11") (pinfunction "PA5_11") (pintype "bidirectional"))
    )
    (net (code "71") (name "unconnected-(U1-PA6-Pad12)") (class "Default")
      (node (ref "U1") (pin "12") (pinfunction "PA6_12") (pintype "bidirectional"))
    )
    (net (code "72") (name "unconnected-(U1-PA7-Pad13)") (class "Default")
      (node (ref "U1") (pin "13") (pinfunction "PA7_13") (pintype "bidirectional"))
    )
    (net (code "73") (name "unconnected-(U1-PA15-Pad23)") (class "Default")
      (node (ref "U1") (pin "23") (pinfunction "PA15_23") (pintype "bidirectional"))
    )
    (net (code "74") (name "unconnected-(U1-PB5-Pad26)") (class "Default")
      (node (ref "U1") (pin "26") (pinfunction "PB5_26") (pintype "bidirectional"))
    )
    (net (code "75") (name "unconnected-(U2-R-Pad4)") (class "Default")
      (node (ref "U2") (pin "4") (pinfunction "R_4") (pintype "output+no_connect"))
    )
    (net (code "76") (name "unconnected-(U3-D-Pad1)") (class "Default")
      (node (ref "U3") (pin "1") (pinfunction "D_1") (pintype "input+no_connect"))
    )
    (net (code "77") (name "unconnected-(U6-PA0-Pad6)") (class "Default")
      (node (ref "U6") (pin "6") (pinfunction "PA0_6") (pintype "bidirectional"))
    )
    (net (code "78") (name "unconnected-(U6-PA1-Pad7)") (class "Default")
      (node (ref "U6") (pin "7") (pinfunction "PA1_7") (pintype "bidirectional"))
    )
    (net (code "79") (name "unconnected-(U6-PA2-Pad8)") (class "Default")
      (node (ref "U6") (pin "8") (pinfunction "PA2_8") (pintype "bidirectional"))
    )
    (net (code "80") (name "unconnected-(U6-PA3-Pad9)") (class "Default")
      (node (ref "U6") (pin "9") (pinfunction "PA3_9") (pintype "bidirectional"))
    )
    (net (code "81") (name "unconnected-(U6-PA4-Pad10)") (class "Default")
      (node (ref "U6") (pin "10") (pinfunction "PA4_10") (pintype "bidirectional"))
    )
    (net (code "82") (name "unconnected-(U6-PA5-Pad11)") (class "Default")
      (node (ref "U6") (pin "11") (pinfunction "PA5_11") (pintype "bidirectional"))
    )
    (net (code "83") (name "unconnected-(U6-PA6-Pad12)") (class "Default")
      (node (ref "U6") (pin "12") (pinfunction "PA6_12") (pintype "bidirectional"))
    )
    (net (code "84") (name "unconnected-(U6-PA7-Pad13)") (class "Default")
      (node (ref "U6") (pin "13") (pinfunction "PA7_13") (pintype "bidirectional"))
    )
    (net (code "85") (name "unconnected-(U6-PA15-Pad23)") (class "Default")
      (node (ref "U6") (pin "23") (pinfunction "PA15_23") (pintype "bidirectional"))
    )
    (net (code "86") (name "unconnected-(U6-PB3-Pad24)") (class "Default")
      (node (ref "U6") (pin "24") (pinfunction "PB3_24") (pintype "bidirectional"))
    )
    (net (code "87") (name "unconnected-(U6-PB5-Pad26)") (class "Default")
      (node (ref "U6") (pin "26") (pinfunction "PB5_26") (pintype "bidirectional"))
    )
    (net (code "88") (name "unconnected-(U7B-N.C.-Pad2)") (class "Default")
      (node (ref "U7") (pin "2") (pinfunction "N.C._2") (pintype "passive"))
    )
    (net (code "89") (name "unconnected-(U7B-N.C.-Pad4)") (class "Default")
      (node (ref "U7") (pin "4") (pinfunction "N.C._4") (pintype "passive"))
    )
    (net (code "90") (name "unconnected-(U7B-N.C.-Pad6)") (class "Default")
      (node (ref "U7") (pin "6") (pinfunction "N.C._6") (pintype "passive"))
    )
    (net (code "91") (name "unconnected-(U7B-N.C.-Pad7)") (class "Default")
      (node (ref "U7") (pin "7") (pinfunction "N.C._7") (pintype "passive"))
    )
    (net (code "92") (name "unconnected-(U7B-N.C.-Pad8)") (class "Default")
      (node (ref "U7") (pin "8") (pinfunction "N.C._8") (pintype "passive"))
    )
    (net (code "93") (name "unconnected-(U7B-N.C.-Pad10)") (class "Default")
      (node (ref "U7") (pin "10") (pinfunction "N.C._10") (pintype "passive"))
    )
  )
)
